# Sheet1.net
KiCad netlist of a schematic drawn in Altium Designer
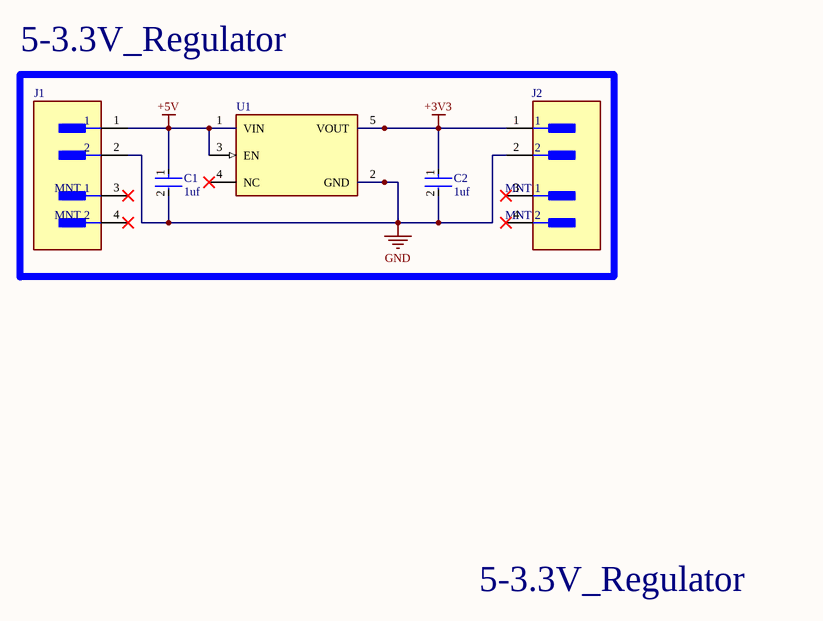
[diagram p0: Sheet1.SchDoc]

(export (version "E")
  (design (tool "Eeschema 10.0.6"))
  (components
    (comp (ref "C1")
      (value "1uf")
      (footprint "FP-CC1206-1_25-MFG")
      (description "CAP CER 1UF 10V X7R 1206")
      (fields
        (field (name "MANUFACTURER") "Yageo")
        (field (name "OCTOPART") "https://octopart.com/cc1206kkx7r6bb105-yageo-21769912")
      )
      (libsource (lib "Altium Content Vault") (part "11868f565c42a9108669ba33697ecf6"))
    )
    (comp (ref "C2")
      (value "1uf")
      (footprint "FP-CC1206-1_25-MFG")
      (description "CAP CER 1UF 10V X7R 1206")
      (fields
        (field (name "MANUFACTURER") "Yageo")
        (field (name "OCTOPART") "https://octopart.com/cc1206kkx7r6bb105-yageo-21769912")
      )
      (libsource (lib "Altium Content Vault") (part "11868f565c42a9108669ba33697ecf6"))
    )
    (comp (ref "J1")
      (value "SM02B-GHS-TB(LF)(SN)")
      (footprint "FP-SM02B-GHS-TB_LF_SN-MFG")
      (description "CONN HEADER SMD R/A 2POS 1.25MM")
      (libsource (lib "") (part "56ec3178a87b3978bdc1b3682cd516a_1"))
    )
    (comp (ref "J2")
      (value "SM02B-GHS-TB(LF)(SN)")
      (footprint "FP-SM02B-GHS-TB_LF_SN-MFG")
      (description "CONN HEADER SMD R/A 2POS 1.25MM")
      (libsource (lib "Altium Content Vault") (part "56ec3178a87b3978bdc1b3682cd516a"))
    )
    (comp (ref "U1")
      (value "MIC5317-3.3YM5-TR")
      (footprint "FP-SOT23-5LD-PL-1-MFG")
      (description "IC REG LINEAR 3.3V 150MA SOT23-5")
      (libsource (lib "Altium Content Vault") (part "0a093dae7315cdc977fd108dde87457"))
    )
  )
  (nets
    (net (code "1") (name "+3V3") (class "Default")
      (node (ref "C2") (pin "1") (pinfunction "1_1") (pintype "passive"))
      (node (ref "J2") (pin "1") (pinfunction "1_1") (pintype "passive"))
      (node (ref "U1") (pin "5") (pinfunction "VOUT_5") (pintype "power_in"))
    )
    (net (code "2") (name "+5V") (class "Default")
      (node (ref "C1") (pin "1") (pinfunction "1_1") (pintype "passive"))
      (node (ref "J1") (pin "1") (pinfunction "1_1") (pintype "passive"))
      (node (ref "U1") (pin "1") (pinfunction "VIN_1") (pintype "power_in"))
      (node (ref "U1") (pin "3") (pinfunction "EN_3") (pintype "input"))
    )
    (net (code "3") (name "GND") (class "Default")
      (node (ref "C1") (pin "2") (pinfunction "2_2") (pintype "passive"))
      (node (ref "C2") (pin "2") (pinfunction "2_2") (pintype "passive"))
      (node (ref "J1") (pin "2") (pinfunction "2_2") (pintype "passive"))
      (node (ref "J2") (pin "2") (pinfunction "2_2") (pintype "passive"))
      (node (ref "U1") (pin "2") (pinfunction "GND_2") (pintype "power_in"))
    )
    (net (code "4") (name "unconnected-(J1-MNT_1-Pad3)") (class "Default")
      (node (ref "J1") (pin "3") (pinfunction "MNT_1_3") (pintype "passive+no_connect"))
    )
    (net (code "5") (name "unconnected-(J1-MNT_2-Pad4)") (class "Default")
      (node (ref "J1") (pin "4") (pinfunction "MNT_2_4") (pintype "passive+no_connect"))
    )
    (net (code "6") (name "unconnected-(J2-MNT_1-Pad3)") (class "Default")
      (node (ref "J2") (pin "3") (pinfunction "MNT_1_3") (pintype "passive+no_connect"))
    )
    (net (code "7") (name "unconnected-(J2-MNT_2-Pad4)") (class "Default")
      (node (ref "J2") (pin "4") (pinfunction "MNT_2_4") (pintype "passive+no_connect"))
    )
    (net (code "8") (name "unconnected-(U1-NC-Pad4)") (class "Default")
      (node (ref "U1") (pin "4") (pinfunction "NC_4") (pintype "passive+no_connect"))
    )
  )
)
